# sensor-breakout.net
KiCad netlist of a schematic drawn in EAGLE
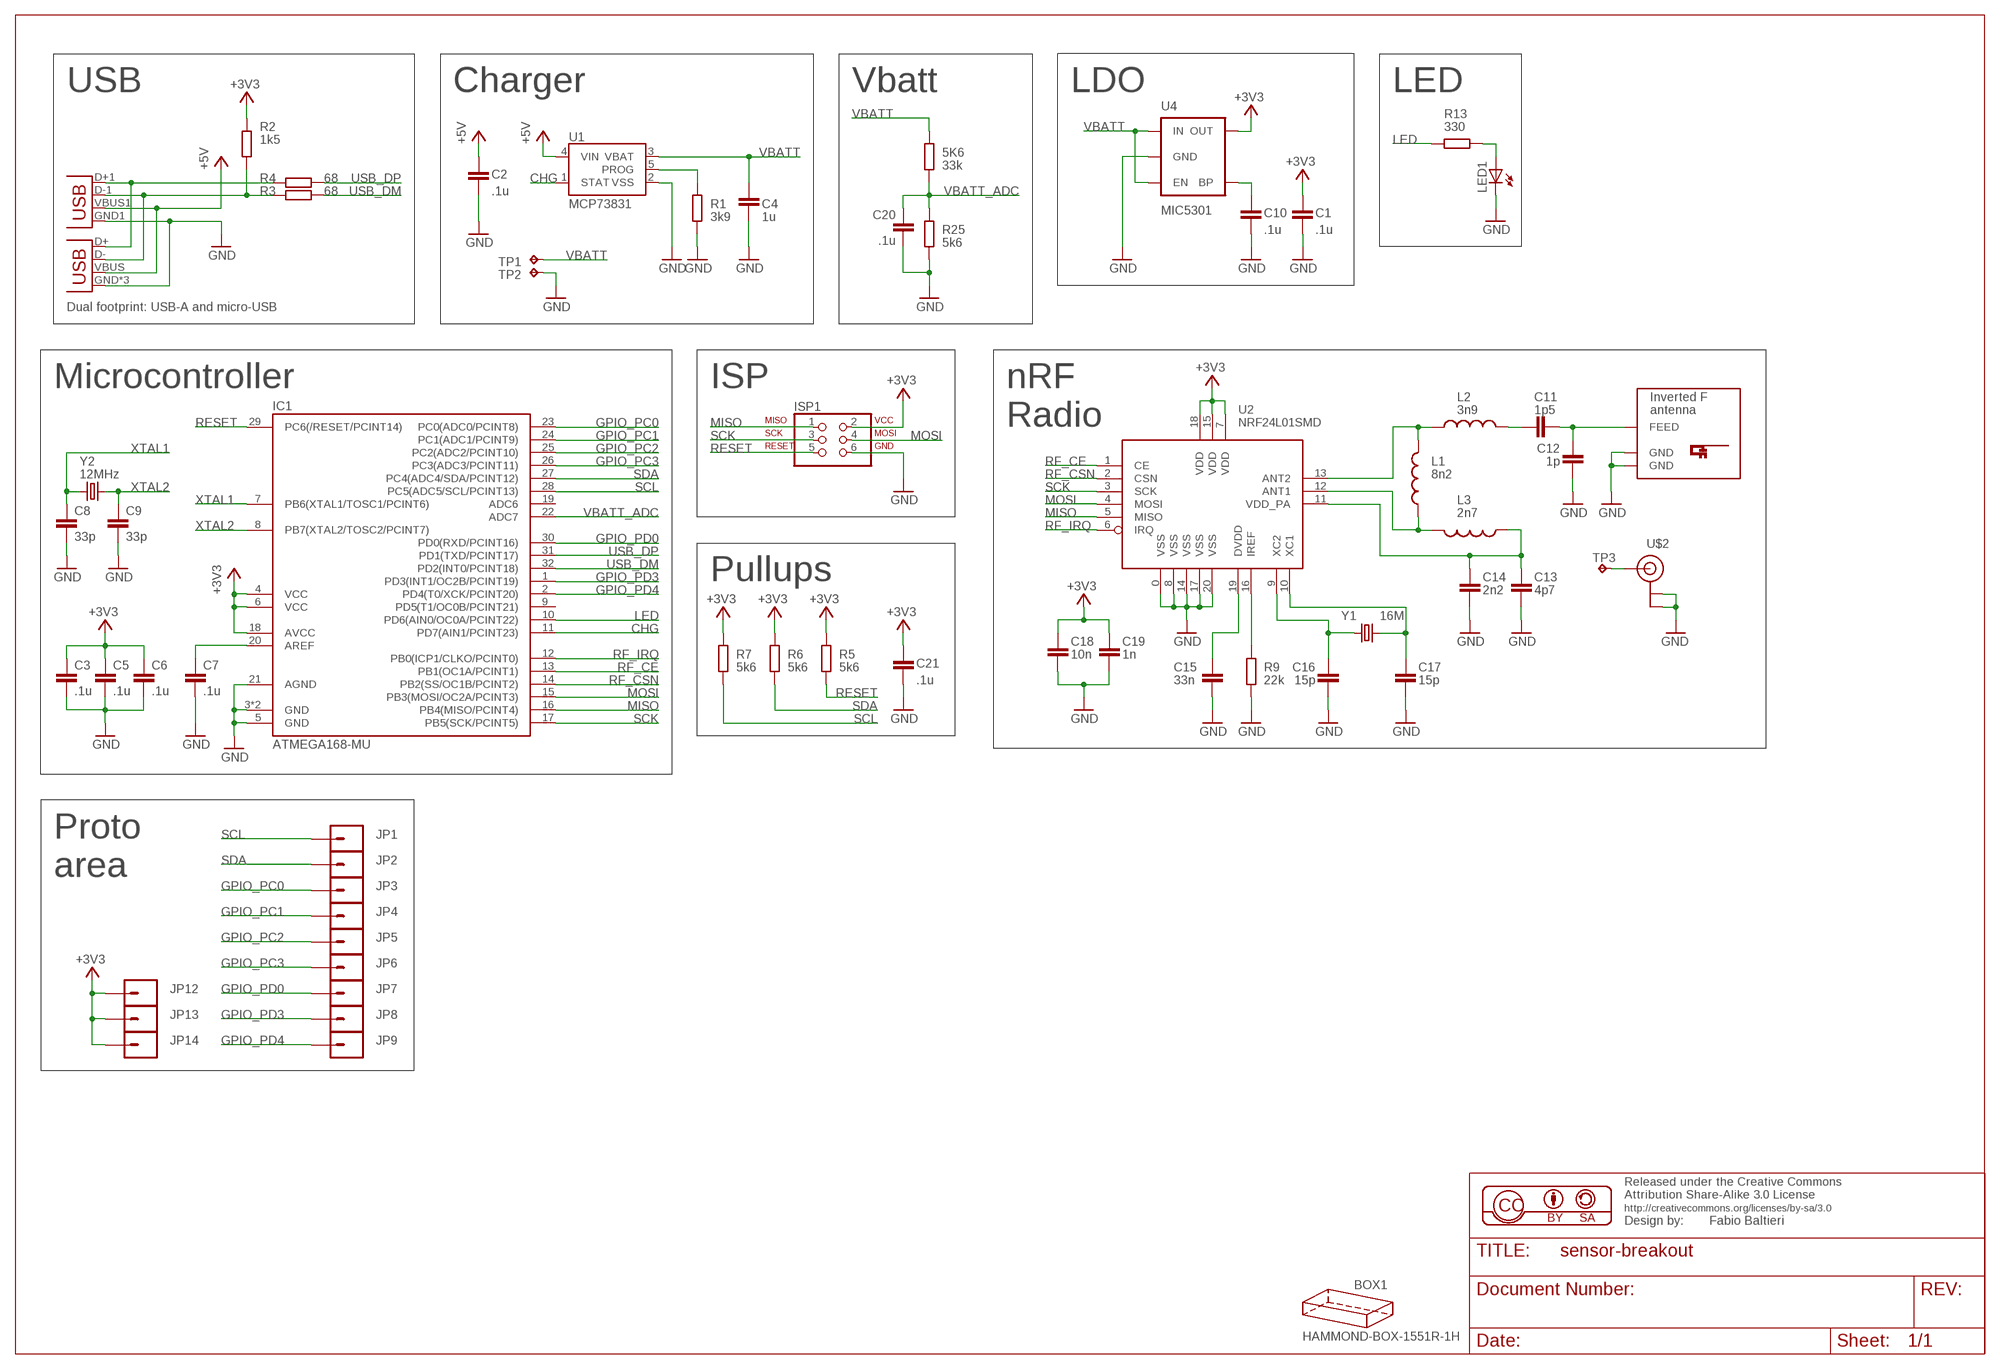
[diagram p0: schematic, sheet 1]

(export (version "E")
  (design (tool "Eeschema 10.0.6"))
  (components
    (comp (ref "5K6")
      (value "33k")
      (footprint "eagle-import:R0603")
      (libsource (lib "eagle-import") (part "R-EU_R0603"))
    )
    (comp (ref "BOX1")
      (value "HAMMOND-BOX-1551R-1H")
      (footprint "eagle-import:1551R-1HOLE")
      (libsource (lib "eagle-import") (part "HAMMOND-BOX-1551R-1H"))
    )
    (comp (ref "C1")
      (value ".1u")
      (footprint "eagle-import:C0603")
      (libsource (lib "eagle-import") (part "C-EUC0603"))
    )
    (comp (ref "C2")
      (value ".1u")
      (footprint "eagle-import:C0603")
      (libsource (lib "eagle-import") (part "C-EUC0603"))
    )
    (comp (ref "C3")
      (value ".1u")
      (footprint "eagle-import:C0603")
      (libsource (lib "eagle-import") (part "C-EUC0603"))
    )
    (comp (ref "C4")
      (value "1u")
      (footprint "eagle-import:C0603")
      (libsource (lib "eagle-import") (part "C-EUC0603"))
    )
    (comp (ref "C5")
      (value ".1u")
      (footprint "eagle-import:C0603")
      (libsource (lib "eagle-import") (part "C-EUC0603"))
    )
    (comp (ref "C6")
      (value ".1u")
      (footprint "eagle-import:C0603")
      (libsource (lib "eagle-import") (part "C-EUC0603"))
    )
    (comp (ref "C7")
      (value ".1u")
      (footprint "eagle-import:C0603")
      (libsource (lib "eagle-import") (part "C-EUC0603"))
    )
    (comp (ref "C8")
      (value "33p")
      (footprint "eagle-import:C0603")
      (libsource (lib "eagle-import") (part "C-EUC0603"))
    )
    (comp (ref "C9")
      (value "33p")
      (footprint "eagle-import:C0603")
      (libsource (lib "eagle-import") (part "C-EUC0603"))
    )
    (comp (ref "C10")
      (value ".1u")
      (footprint "eagle-import:C0603")
      (libsource (lib "eagle-import") (part "C-EUC0603"))
    )
    (comp (ref "C11")
      (value "1p5")
      (footprint "eagle-import:C0603")
      (libsource (lib "eagle-import") (part "C-EUC0603"))
    )
    (comp (ref "C12")
      (value "1p")
      (footprint "eagle-import:C0603")
      (libsource (lib "eagle-import") (part "C-EUC0603"))
    )
    (comp (ref "C13")
      (value "4p7")
      (footprint "eagle-import:C0603")
      (libsource (lib "eagle-import") (part "C-EUC0603"))
    )
    (comp (ref "C14")
      (value "2n2")
      (footprint "eagle-import:C0603")
      (libsource (lib "eagle-import") (part "C-EUC0603"))
    )
    (comp (ref "C15")
      (value "33n")
      (footprint "eagle-import:C0603")
      (libsource (lib "eagle-import") (part "C-EUC0603"))
    )
    (comp (ref "C16")
      (value "15p")
      (footprint "eagle-import:C0603")
      (libsource (lib "eagle-import") (part "C-EUC0603"))
    )
    (comp (ref "C17")
      (value "15p")
      (footprint "eagle-import:C0603")
      (libsource (lib "eagle-import") (part "C-EUC0603"))
    )
    (comp (ref "C18")
      (value "10n")
      (footprint "eagle-import:C0603")
      (libsource (lib "eagle-import") (part "C-EUC0603"))
    )
    (comp (ref "C19")
      (value "1n")
      (footprint "eagle-import:C0603")
      (libsource (lib "eagle-import") (part "C-EUC0603"))
    )
    (comp (ref "C20")
      (value ".1u")
      (footprint "eagle-import:C0603")
      (libsource (lib "eagle-import") (part "C-EUC0603"))
    )
    (comp (ref "C21")
      (value ".1u")
      (footprint "eagle-import:C0603")
      (libsource (lib "eagle-import") (part "C-EUC0603"))
    )
    (comp (ref "IC1")
      (value "ATMEGA168-MU")
      (footprint "eagle-import:MLF32-TH")
      (libsource (lib "eagle-import") (part "ATMEGA168-MU"))
    )
    (comp (ref "ISP1")
      (value "ISP-AVR910PTH")
      (footprint "eagle-import:2X03")
      (libsource (lib "eagle-import") (part "ISP-AVR910PTH"))
    )
    (comp (ref "JP1")
      (value "M01NOSILK-KIT")
      (footprint "eagle-import:1X01NS-KIT")
      (libsource (lib "eagle-import") (part "M01NOSILK-KIT"))
    )
    (comp (ref "JP2")
      (value "M01NOSILK-KIT")
      (footprint "eagle-import:1X01NS-KIT")
      (libsource (lib "eagle-import") (part "M01NOSILK-KIT"))
    )
    (comp (ref "JP3")
      (value "M01NOSILK-KIT")
      (footprint "eagle-import:1X01NS-KIT")
      (libsource (lib "eagle-import") (part "M01NOSILK-KIT"))
    )
    (comp (ref "JP4")
      (value "M01NOSILK-KIT")
      (footprint "eagle-import:1X01NS-KIT")
      (libsource (lib "eagle-import") (part "M01NOSILK-KIT"))
    )
    (comp (ref "JP5")
      (value "M01NOSILK-KIT")
      (footprint "eagle-import:1X01NS-KIT")
      (libsource (lib "eagle-import") (part "M01NOSILK-KIT"))
    )
    (comp (ref "JP6")
      (value "M01NOSILK-KIT")
      (footprint "eagle-import:1X01NS-KIT")
      (libsource (lib "eagle-import") (part "M01NOSILK-KIT"))
    )
    (comp (ref "JP7")
      (value "M01NOSILK-KIT")
      (footprint "eagle-import:1X01NS-KIT")
      (libsource (lib "eagle-import") (part "M01NOSILK-KIT"))
    )
    (comp (ref "JP8")
      (value "M01NOSILK-KIT")
      (footprint "eagle-import:1X01NS-KIT")
      (libsource (lib "eagle-import") (part "M01NOSILK-KIT"))
    )
    (comp (ref "JP9")
      (value "M01NOSILK-KIT")
      (footprint "eagle-import:1X01NS-KIT")
      (libsource (lib "eagle-import") (part "M01NOSILK-KIT"))
    )
    (comp (ref "JP10")
      (value "USB-MICROB")
      (footprint "eagle-import:USB-MICROB")
      (libsource (lib "eagle-import") (part "USB-MICROB"))
    )
    (comp (ref "JP11")
      (value "USBA-SMD-MALE")
      (footprint "eagle-import:USB-A-SMT-MALE")
      (libsource (lib "eagle-import") (part "USBA-SMD-MALE"))
    )
    (comp (ref "JP12")
      (value "M01NOSILK-KIT")
      (footprint "eagle-import:1X01NS-KIT")
      (libsource (lib "eagle-import") (part "M01NOSILK-KIT"))
    )
    (comp (ref "JP13")
      (value "M01NOSILK-KIT")
      (footprint "eagle-import:1X01NS-KIT")
      (libsource (lib "eagle-import") (part "M01NOSILK-KIT"))
    )
    (comp (ref "JP14")
      (value "M01NOSILK-KIT")
      (footprint "eagle-import:1X01NS-KIT")
      (libsource (lib "eagle-import") (part "M01NOSILK-KIT"))
    )
    (comp (ref "L1")
      (value "8n2")
      (footprint "eagle-import:0603")
      (libsource (lib "eagle-import") (part "INDUCTOR0603"))
    )
    (comp (ref "L2")
      (value "3n9")
      (footprint "eagle-import:0603")
      (libsource (lib "eagle-import") (part "INDUCTOR0603"))
    )
    (comp (ref "L3")
      (value "2n7")
      (footprint "eagle-import:0603")
      (libsource (lib "eagle-import") (part "INDUCTOR0603"))
    )
    (comp (ref "LED1")
      (value "LEDSML0805")
      (footprint "eagle-import:SML0805")
      (libsource (lib "eagle-import") (part "LEDSML0805"))
    )
    (comp (ref "R1")
      (value "3k9")
      (footprint "eagle-import:R0603")
      (libsource (lib "eagle-import") (part "R-EU_R0603"))
    )
    (comp (ref "R2")
      (value "1k5")
      (footprint "eagle-import:R0603")
      (libsource (lib "eagle-import") (part "R-EU_R0603"))
    )
    (comp (ref "R3")
      (value "68")
      (footprint "eagle-import:R0603")
      (libsource (lib "eagle-import") (part "R-EU_R0603"))
    )
    (comp (ref "R4")
      (value "68")
      (footprint "eagle-import:R0603")
      (libsource (lib "eagle-import") (part "R-EU_R0603"))
    )
    (comp (ref "R5")
      (value "5k6")
      (footprint "eagle-import:R0603")
      (libsource (lib "eagle-import") (part "R-EU_R0603"))
    )
    (comp (ref "R6")
      (value "5k6")
      (footprint "eagle-import:R0603")
      (libsource (lib "eagle-import") (part "R-EU_R0603"))
    )
    (comp (ref "R7")
      (value "5k6")
      (footprint "eagle-import:R0603")
      (libsource (lib "eagle-import") (part "R-EU_R0603"))
    )
    (comp (ref "R9")
      (value "22k")
      (footprint "eagle-import:R0603")
      (libsource (lib "eagle-import") (part "R-EU_R0603"))
    )
    (comp (ref "R13")
      (value "330")
      (footprint "eagle-import:R0603")
      (libsource (lib "eagle-import") (part "R-EU_R0603"))
    )
    (comp (ref "R25")
      (value "5k6")
      (footprint "eagle-import:R0603")
      (libsource (lib "eagle-import") (part "R-EU_R0603"))
    )
    (comp (ref "TP1")
      (value "TPTP12R")
      (footprint "eagle-import:TP12R")
      (libsource (lib "eagle-import") (part "TPTP12R"))
    )
    (comp (ref "TP2")
      (value "TPTP12R")
      (footprint "eagle-import:TP12R")
      (libsource (lib "eagle-import") (part "TPTP12R"))
    )
    (comp (ref "TP3")
      (value "TPTP08SQ")
      (footprint "eagle-import:TP08SQ")
      (libsource (lib "eagle-import") (part "TPTP08SQ"))
    )
    (comp (ref "U$1")
      (value "INVERTED_F_ANTENNA-2")
      (footprint "eagle-import:DN007-2")
      (libsource (lib "eagle-import") (part "INVERTED_F_ANTENNA-2"))
    )
    (comp (ref "U$2")
      (value "U.FL")
      (footprint "eagle-import:U.FL")
      (libsource (lib "eagle-import") (part "U.FL"))
    )
    (comp (ref "U1")
      (value "MCP73831")
      (footprint "eagle-import:SOT23-5")
      (libsource (lib "eagle-import") (part "MCP73831"))
    )
    (comp (ref "U2")
      (value "NRF24L01SMD")
      (footprint "eagle-import:QFN20")
      (libsource (lib "eagle-import") (part "NRF24L01SMD"))
    )
    (comp (ref "U4")
      (value "MIC5301")
      (footprint "eagle-import:SOT23-5")
      (libsource (lib "eagle-import") (part "V_REG_LDOSMD"))
    )
    (comp (ref "Y1")
      (value "16M")
      (footprint "eagle-import:CRYSTAL-SMD-5X3")
      (libsource (lib "eagle-import") (part "CRYSTAL5X3"))
    )
    (comp (ref "Y2")
      (value "12MHz")
      (footprint "eagle-import:CRYSTAL-SMD-5X3")
      (libsource (lib "eagle-import") (part "SparkFun-FreqCtrl_CRYSTAL5X3"))
    )
  )
  (nets
    (net (code "1") (name "+3V3") (class "Default")
      (node (ref "C1") (pin "1") (pinfunction "1_1") (pintype "passive"))
      (node (ref "C18") (pin "1") (pinfunction "1_1") (pintype "passive"))
      (node (ref "C19") (pin "1") (pinfunction "1_1") (pintype "passive"))
      (node (ref "C21") (pin "1") (pinfunction "1_1") (pintype "passive"))
      (node (ref "C3") (pin "1") (pinfunction "1_1") (pintype "passive"))
      (node (ref "C5") (pin "1") (pinfunction "1_1") (pintype "passive"))
      (node (ref "C6") (pin "1") (pinfunction "1_1") (pintype "passive"))
      (node (ref "IC1") (pin "18") (pinfunction "AVCC_18") (pintype "passive"))
      (node (ref "IC1") (pin "4") (pinfunction "VCC_4") (pintype "power_in"))
      (node (ref "IC1") (pin "6") (pinfunction "VCC_6") (pintype "power_in"))
      (node (ref "ISP1") (pin "2") (pinfunction "2_2") (pintype "passive"))
      (node (ref "JP12") (pin "1") (pinfunction "1_1") (pintype "passive"))
      (node (ref "JP13") (pin "1") (pinfunction "1_1") (pintype "passive"))
      (node (ref "JP14") (pin "1") (pinfunction "1_1") (pintype "passive"))
      (node (ref "R2") (pin "2") (pinfunction "2_2") (pintype "passive"))
      (node (ref "R5") (pin "1") (pinfunction "1_1") (pintype "passive"))
      (node (ref "R6") (pin "1") (pinfunction "1_1") (pintype "passive"))
      (node (ref "R7") (pin "1") (pinfunction "1_1") (pintype "passive"))
      (node (ref "U2") (pin "15") (pinfunction "VDD_15") (pintype "power_in"))
      (node (ref "U2") (pin "18") (pinfunction "VDD_18") (pintype "power_in"))
      (node (ref "U2") (pin "7") (pinfunction "VDD_7") (pintype "power_in"))
      (node (ref "U4") (pin "5") (pinfunction "OUT_5") (pintype "passive"))
    )
    (net (code "2") (name "+5V") (class "Default")
      (node (ref "C2") (pin "1") (pinfunction "1_1") (pintype "passive"))
      (node (ref "JP10") (pin "VBUS") (pinfunction "VBUS_VBUS") (pintype "bidirectional"))
      (node (ref "JP11") (pin "VBUS1") (pinfunction "VBUS_VBUS1") (pintype "bidirectional"))
      (node (ref "U1") (pin "4") (pinfunction "VIN_4") (pintype "power_in"))
    )
    (net (code "3") (name "/CHG") (class "Default")
      (node (ref "IC1") (pin "11") (pinfunction "PD7(AIN1/PCINT23)_11") (pintype "bidirectional"))
      (node (ref "U1") (pin "1") (pinfunction "STAT_1") (pintype "output"))
    )
    (net (code "4") (name "/GPIO_PC0") (class "Default")
      (node (ref "IC1") (pin "23") (pinfunction "PC0(ADC0/PCINT8)_23") (pintype "bidirectional"))
      (node (ref "JP3") (pin "1") (pinfunction "1_1") (pintype "passive"))
    )
    (net (code "5") (name "/GPIO_PC1") (class "Default")
      (node (ref "IC1") (pin "24") (pinfunction "PC1(ADC1/PCINT9)_24") (pintype "bidirectional"))
      (node (ref "JP4") (pin "1") (pinfunction "1_1") (pintype "passive"))
    )
    (net (code "6") (name "/GPIO_PC2") (class "Default")
      (node (ref "IC1") (pin "25") (pinfunction "PC2(ADC2/PCINT10)_25") (pintype "bidirectional"))
      (node (ref "JP5") (pin "1") (pinfunction "1_1") (pintype "passive"))
    )
    (net (code "7") (name "/GPIO_PC3") (class "Default")
      (node (ref "IC1") (pin "26") (pinfunction "PC3(ADC3/PCINT11)_26") (pintype "bidirectional"))
      (node (ref "JP6") (pin "1") (pinfunction "1_1") (pintype "passive"))
    )
    (net (code "8") (name "/GPIO_PD0") (class "Default")
      (node (ref "IC1") (pin "30") (pinfunction "PD0(RXD/PCINT16)_30") (pintype "bidirectional"))
      (node (ref "JP7") (pin "1") (pinfunction "1_1") (pintype "passive"))
    )
    (net (code "9") (name "/GPIO_PD3") (class "Default")
      (node (ref "IC1") (pin "1") (pinfunction "PD3(INT1/OC2B/PCINT19)_1") (pintype "bidirectional"))
      (node (ref "JP8") (pin "1") (pinfunction "1_1") (pintype "passive"))
    )
    (net (code "10") (name "/GPIO_PD4") (class "Default")
      (node (ref "IC1") (pin "2") (pinfunction "PD4(T0/XCK/PCINT20)_2") (pintype "bidirectional"))
      (node (ref "JP9") (pin "1") (pinfunction "1_1") (pintype "passive"))
    )
    (net (code "11") (name "/LED") (class "Default")
      (node (ref "IC1") (pin "10") (pinfunction "PD6(AIN0/OC0A/PCINT22)_10") (pintype "bidirectional"))
      (node (ref "R13") (pin "2") (pinfunction "2_2") (pintype "passive"))
    )
    (net (code "12") (name "/MISO") (class "Default")
      (node (ref "IC1") (pin "16") (pinfunction "PB4(MISO/PCINT4)_16") (pintype "bidirectional"))
      (node (ref "ISP1") (pin "1") (pinfunction "1_1") (pintype "passive"))
      (node (ref "U2") (pin "5") (pinfunction "MISO_5") (pintype "output"))
    )
    (net (code "13") (name "/MOSI") (class "Default")
      (node (ref "IC1") (pin "15") (pinfunction "PB3(MOSI/OC2A/PCINT3)_15") (pintype "bidirectional"))
      (node (ref "ISP1") (pin "4") (pinfunction "4_4") (pintype "passive"))
      (node (ref "U2") (pin "4") (pinfunction "MOSI_4") (pintype "input"))
    )
    (net (code "14") (name "/RESET") (class "Default")
      (node (ref "IC1") (pin "29") (pinfunction "PC6(/RESET/PCINT14)_29") (pintype "bidirectional"))
      (node (ref "ISP1") (pin "5") (pinfunction "5_5") (pintype "passive"))
      (node (ref "R5") (pin "2") (pinfunction "2_2") (pintype "passive"))
    )
    (net (code "15") (name "/RF_CE") (class "Default")
      (node (ref "IC1") (pin "13") (pinfunction "PB1(OC1A/PCINT1)_13") (pintype "bidirectional"))
      (node (ref "U2") (pin "1") (pinfunction "CE_1") (pintype "input"))
    )
    (net (code "16") (name "/RF_CSN") (class "Default")
      (node (ref "IC1") (pin "14") (pinfunction "PB2(SS/OC1B/PCINT2)_14") (pintype "bidirectional"))
      (node (ref "U2") (pin "2") (pinfunction "CSN_2") (pintype "input"))
    )
    (net (code "17") (name "/RF_IRQ") (class "Default")
      (node (ref "IC1") (pin "12") (pinfunction "PB0(ICP1/CLKO/PCINT0)_12") (pintype "bidirectional"))
      (node (ref "U2") (pin "6") (pinfunction "IRQ_6") (pintype "output"))
    )
    (net (code "18") (name "/SCK") (class "Default")
      (node (ref "IC1") (pin "17") (pinfunction "PB5(SCK/PCINT5)_17") (pintype "bidirectional"))
      (node (ref "ISP1") (pin "3") (pinfunction "3_3") (pintype "passive"))
      (node (ref "U2") (pin "3") (pinfunction "SCK_3") (pintype "input"))
    )
    (net (code "19") (name "/SCL") (class "Default")
      (node (ref "IC1") (pin "28") (pinfunction "PC5(ADC5/SCL/PCINT13)_28") (pintype "bidirectional"))
      (node (ref "JP1") (pin "1") (pinfunction "1_1") (pintype "passive"))
      (node (ref "R7") (pin "2") (pinfunction "2_2") (pintype "passive"))
    )
    (net (code "20") (name "/SDA") (class "Default")
      (node (ref "IC1") (pin "27") (pinfunction "PC4(ADC4/SDA/PCINT12)_27") (pintype "bidirectional"))
      (node (ref "JP2") (pin "1") (pinfunction "1_1") (pintype "passive"))
      (node (ref "R6") (pin "2") (pinfunction "2_2") (pintype "passive"))
    )
    (net (code "21") (name "/USB_DM") (class "Default")
      (node (ref "IC1") (pin "32") (pinfunction "PD2(INT0/PCINT18)_32") (pintype "bidirectional"))
      (node (ref "R3") (pin "1") (pinfunction "1_1") (pintype "passive"))
    )
    (net (code "22") (name "/USB_DP") (class "Default")
      (node (ref "IC1") (pin "31") (pinfunction "PD1(TXD/PCINT17)_31") (pintype "bidirectional"))
      (node (ref "R4") (pin "1") (pinfunction "1_1") (pintype "passive"))
    )
    (net (code "23") (name "/VBATT") (class "Default")
      (node (ref "5K6") (pin "1") (pinfunction "1_1") (pintype "passive"))
      (node (ref "C4") (pin "1") (pinfunction "1_1") (pintype "passive"))
      (node (ref "TP1") (pin "TP") (pinfunction "TP_TP") (pintype "input"))
      (node (ref "U1") (pin "3") (pinfunction "VBAT_3") (pintype "power_in"))
      (node (ref "U4") (pin "1") (pinfunction "IN_1") (pintype "input"))
      (node (ref "U4") (pin "3") (pinfunction "EN_3") (pintype "input"))
    )
    (net (code "24") (name "/VBATT_ADC") (class "Default")
      (node (ref "5K6") (pin "2") (pinfunction "2_2") (pintype "passive"))
      (node (ref "C20") (pin "1") (pinfunction "1_1") (pintype "passive"))
      (node (ref "IC1") (pin "22") (pinfunction "ADC7_22") (pintype "passive"))
      (node (ref "R25") (pin "1") (pinfunction "1_1") (pintype "passive"))
    )
    (net (code "25") (name "/XTAL1") (class "Default")
      (node (ref "C8") (pin "1") (pinfunction "1_1") (pintype "passive"))
      (node (ref "IC1") (pin "7") (pinfunction "PB6(XTAL1/TOSC1/PCINT6)_7") (pintype "bidirectional"))
      (node (ref "Y2") (pin "1") (pinfunction "1_1") (pintype "passive"))
    )
    (net (code "26") (name "/XTAL2") (class "Default")
      (node (ref "C9") (pin "1") (pinfunction "1_1") (pintype "passive"))
      (node (ref "IC1") (pin "8") (pinfunction "PB7(XTAL2/TOSC2/PCINT7)_8") (pintype "bidirectional"))
      (node (ref "Y2") (pin "3") (pinfunction "2_3") (pintype "passive"))
    )
    (net (code "27") (name "GND") (class "Default")
      (node (ref "C1") (pin "2") (pinfunction "2_2") (pintype "passive"))
      (node (ref "C10") (pin "2") (pinfunction "2_2") (pintype "passive"))
      (node (ref "C12") (pin "2") (pinfunction "2_2") (pintype "passive"))
      (node (ref "C13") (pin "2") (pinfunction "2_2") (pintype "passive"))
      (node (ref "C14") (pin "2") (pinfunction "2_2") (pintype "passive"))
      (node (ref "C15") (pin "2") (pinfunction "2_2") (pintype "passive"))
      (node (ref "C16") (pin "2") (pinfunction "2_2") (pintype "passive"))
      (node (ref "C17") (pin "2") (pinfunction "2_2") (pintype "passive"))
      (node (ref "C18") (pin "2") (pinfunction "2_2") (pintype "passive"))
      (node (ref "C19") (pin "2") (pinfunction "2_2") (pintype "passive"))
      (node (ref "C2") (pin "2") (pinfunction "2_2") (pintype "passive"))
      (node (ref "C20") (pin "2") (pinfunction "2_2") (pintype "passive"))
      (node (ref "C21") (pin "2") (pinfunction "2_2") (pintype "passive"))
      (node (ref "C3") (pin "2") (pinfunction "2_2") (pintype "passive"))
      (node (ref "C4") (pin "2") (pinfunction "2_2") (pintype "passive"))
      (node (ref "C5") (pin "2") (pinfunction "2_2") (pintype "passive"))
      (node (ref "C6") (pin "2") (pinfunction "2_2") (pintype "passive"))
      (node (ref "C7") (pin "2") (pinfunction "2_2") (pintype "passive"))
      (node (ref "C8") (pin "2") (pinfunction "2_2") (pintype "passive"))
      (node (ref "C9") (pin "2") (pinfunction "2_2") (pintype "passive"))
      (node (ref "IC1") (pin "21") (pinfunction "AGND_21") (pintype "power_in"))
      (node (ref "IC1") (pin "3") (pinfunction "GND_3") (pintype "power_in"))
      (node (ref "IC1") (pin "5") (pinfunction "GND_5") (pintype "power_in"))
      (node (ref "IC1") (pin "TH") (pinfunction "GND_TH") (pintype "power_in"))
      (node (ref "ISP1") (pin "6") (pinfunction "6_6") (pintype "passive"))
      (node (ref "JP10") (pin "GND") (pinfunction "GND_GND") (pintype "bidirectional"))
      (node (ref "JP10") (pin "MT1") (pinfunction "GND_MT1") (pintype "bidirectional"))
      (node (ref "JP10") (pin "MT2") (pinfunction "GND_MT2") (pintype "bidirectional"))
      (node (ref "JP11") (pin "GND1") (pinfunction "GND_GND1") (pintype "bidirectional"))
      (node (ref "LED1") (pin "C") (pinfunction "C_C") (pintype "passive"))
      (node (ref "R1") (pin "2") (pinfunction "2_2") (pintype "passive"))
      (node (ref "R25") (pin "2") (pinfunction "2_2") (pintype "passive"))
      (node (ref "R9") (pin "2") (pinfunction "2_2") (pintype "passive"))
      (node (ref "TP2") (pin "TP") (pinfunction "TP_TP") (pintype "input"))
      (node (ref "U$1") (pin "GND") (pinfunction "GND_GND") (pintype "bidirectional"))
      (node (ref "U$1") (pin "GND@1") (pinfunction "GND_GND@1") (pintype "bidirectional"))
      (node (ref "U$2") (pin "P$1") (pinfunction "GND_P$1") (pintype "bidirectional"))
      (node (ref "U$2") (pin "P$2") (pinfunction "GND_P$2") (pintype "bidirectional"))
      (node (ref "U1") (pin "2") (pinfunction "VSS_2") (pintype "power_in"))
      (node (ref "U2") (pin "0") (pinfunction "VSS_0") (pintype "power_in"))
      (node (ref "U2") (pin "14") (pinfunction "VSS_14") (pintype "power_in"))
      (node (ref "U2") (pin "17") (pinfunction "VSS_17") (pintype "power_in"))
      (node (ref "U2") (pin "20") (pinfunction "VSS_20") (pintype "power_in"))
      (node (ref "U2") (pin "8") (pinfunction "VSS_8") (pintype "power_in"))
      (node (ref "U4") (pin "2") (pinfunction "GND_2") (pintype "input"))
    )
    (net (code "28") (name "Net-(C11-Pad1)") (class "Default")
      (node (ref "C11") (pin "1") (pinfunction "1_1") (pintype "passive"))
      (node (ref "L2") (pin "2") (pinfunction "2_2") (pintype "passive"))
    )
    (net (code "29") (name "Net-(C11-Pad2)") (class "Default")
      (node (ref "C11") (pin "2") (pinfunction "2_2") (pintype "passive"))
      (node (ref "C12") (pin "1") (pinfunction "1_1") (pintype "passive"))
      (node (ref "U$1") (pin "FEED") (pinfunction "FEED_FEED") (pintype "bidirectional"))
    )
    (net (code "30") (name "Net-(IC1-AREF)") (class "Default")
      (node (ref "C7") (pin "1") (pinfunction "1_1") (pintype "passive"))
      (node (ref "IC1") (pin "20") (pinfunction "AREF_20") (pintype "passive"))
    )
    (net (code "31") (name "Net-(JP11-D+)") (class "Default")
      (node (ref "JP10") (pin "D+") (pinfunction "D+_D+") (pintype "bidirectional"))
      (node (ref "JP11") (pin "D+1") (pinfunction "D+_D+1") (pintype "bidirectional"))
      (node (ref "R4") (pin "2") (pinfunction "2_2") (pintype "passive"))
    )
    (net (code "32") (name "Net-(JP11-D-)") (class "Default")
      (node (ref "JP10") (pin "D-") (pinfunction "D-_D-") (pintype "bidirectional"))
      (node (ref "JP11") (pin "D-1") (pinfunction "D-_D-1") (pintype "bidirectional"))
      (node (ref "R2") (pin "1") (pinfunction "1_1") (pintype "passive"))
      (node (ref "R3") (pin "2") (pinfunction "2_2") (pintype "passive"))
    )
    (net (code "33") (name "Net-(LED1-PadA)") (class "Default")
      (node (ref "LED1") (pin "A") (pinfunction "A_A") (pintype "passive"))
      (node (ref "R13") (pin "1") (pinfunction "1_1") (pintype "passive"))
    )
    (net (code "34") (name "Net-(U$2-SIGNAL)") (class "Default")
      (node (ref "TP3") (pin "TP") (pinfunction "TP_TP") (pintype "input"))
      (node (ref "U$2") (pin "P$3") (pinfunction "SIGNAL_P$3") (pintype "bidirectional"))
    )
    (net (code "35") (name "Net-(U1-PROG)") (class "Default")
      (node (ref "R1") (pin "1") (pinfunction "1_1") (pintype "passive"))
      (node (ref "U1") (pin "5") (pinfunction "PROG_5") (pintype "input"))
    )
    (net (code "36") (name "Net-(U2-ANT1)") (class "Default")
      (node (ref "L1") (pin "2") (pinfunction "2_2") (pintype "passive"))
      (node (ref "L3") (pin "2") (pinfunction "2_2") (pintype "passive"))
      (node (ref "U2") (pin "12") (pinfunction "ANT1_12") (pintype "output"))
    )
    (net (code "37") (name "Net-(U2-ANT2)") (class "Default")
      (node (ref "L1") (pin "1") (pinfunction "1_1") (pintype "passive"))
      (node (ref "L2") (pin "1") (pinfunction "1_1") (pintype "passive"))
      (node (ref "U2") (pin "13") (pinfunction "ANT2_13") (pintype "output"))
    )
    (net (code "38") (name "Net-(U2-DVDD)") (class "Default")
      (node (ref "C15") (pin "1") (pinfunction "1_1") (pintype "passive"))
      (node (ref "U2") (pin "19") (pinfunction "DVDD_19") (pintype "power_in"))
    )
    (net (code "39") (name "Net-(U2-IREF)") (class "Default")
      (node (ref "R9") (pin "1") (pinfunction "1_1") (pintype "passive"))
      (node (ref "U2") (pin "16") (pinfunction "IREF_16") (pintype "input"))
    )
    (net (code "40") (name "Net-(U2-VDD_PA)") (class "Default")
      (node (ref "C13") (pin "1") (pinfunction "1_1") (pintype "passive"))
      (node (ref "C14") (pin "1") (pinfunction "1_1") (pintype "passive"))
      (node (ref "L3") (pin "1") (pinfunction "1_1") (pintype "passive"))
      (node (ref "U2") (pin "11") (pinfunction "VDD_PA_11") (pintype "power_in"))
    )
    (net (code "41") (name "Net-(U2-XC1)") (class "Default")
      (node (ref "C17") (pin "1") (pinfunction "1_1") (pintype "passive"))
      (node (ref "U2") (pin "10") (pinfunction "XC1_10") (pintype "input"))
      (node (ref "Y1") (pin "3") (pinfunction "2_3") (pintype "passive"))
    )
    (net (code "42") (name "Net-(U2-XC2)") (class "Default")
      (node (ref "C16") (pin "1") (pinfunction "1_1") (pintype "passive"))
      (node (ref "U2") (pin "9") (pinfunction "XC2_9") (pintype "input"))
      (node (ref "Y1") (pin "1") (pinfunction "1_1") (pintype "passive"))
    )
    (net (code "43") (name "Net-(U4-BP)") (class "Default")
      (node (ref "C10") (pin "1") (pinfunction "1_1") (pintype "passive"))
      (node (ref "U4") (pin "4") (pinfunction "BP_4") (pintype "input"))
    )
    (net (code "44") (name "unconnected-(IC1-ADC6-Pad19)") (class "Default")
      (node (ref "IC1") (pin "19") (pinfunction "ADC6_19") (pintype "passive"))
    )
    (net (code "45") (name "unconnected-(IC1-PD5(T1{slash}OC0B{slash}PCINT21)-Pad9)") (class "Default")
      (node (ref "IC1") (pin "9") (pinfunction "PD5(T1/OC0B/PCINT21)_9") (pintype "bidirectional"))
    )
  )
)
